# TFT-Display.net
KiCad netlist of a schematic drawn in Altium Designer
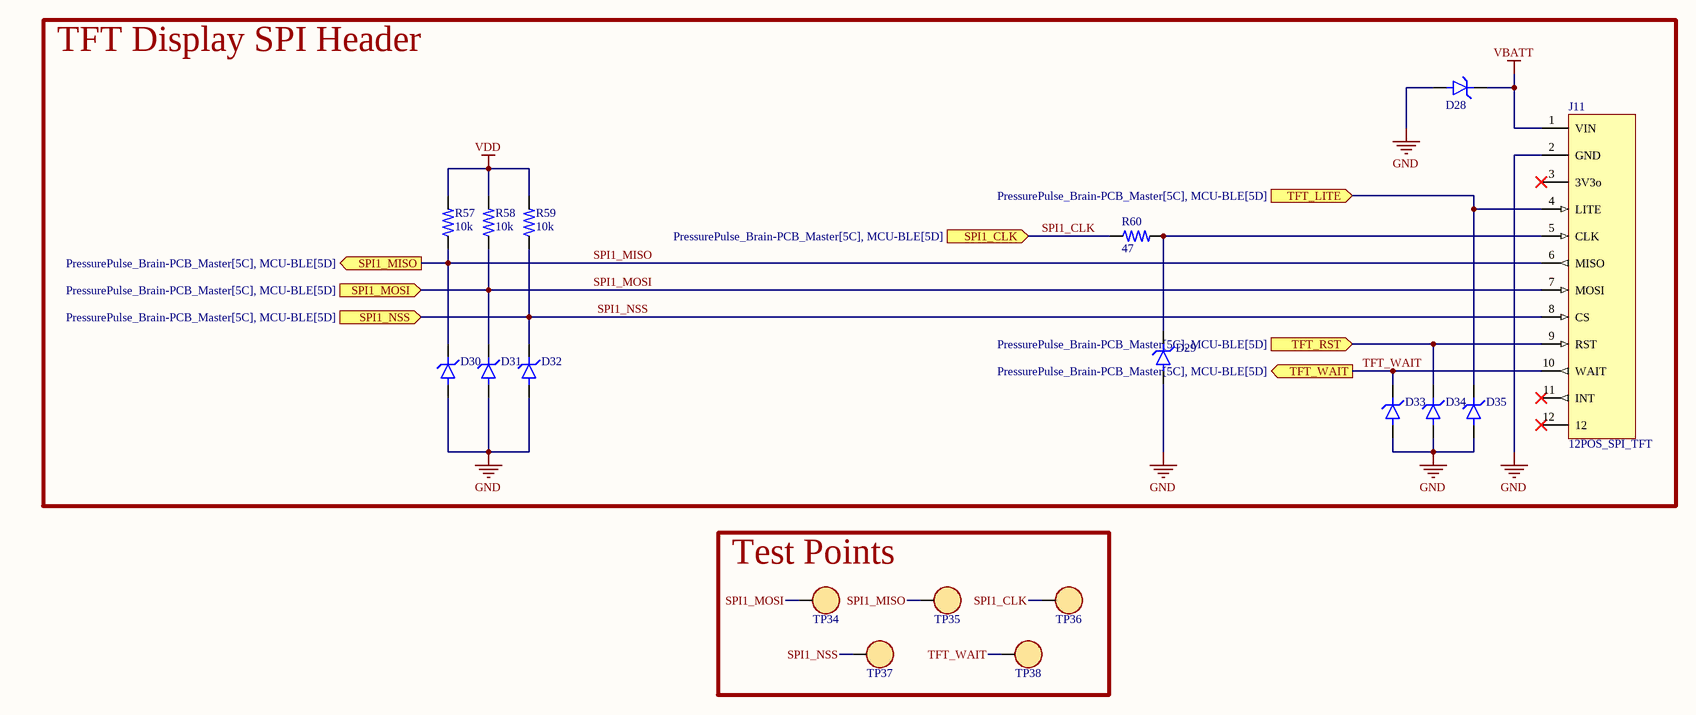
[diagram p0: TFT-Display.SchDoc]

(export (version "E")
  (design (tool "Eeschema 10.0.6"))
  (components
    (comp (ref "D28")
      (value "RCLAMP0521P.TCT")
      (footprint "PressurePulse:BDFN2C051V40")
      (description "25V Clamp 4A (8/20µs) Ipp Tvs Diode Surface Mount SLP1006P2")
      (fields (field (name "MFR") "BORN"))
      (libsource (lib "PressurePulse") (part "TVS DIODE"))
    )
    (comp (ref "D29")
      (value "RCLAMP0521P.TCT")
      (footprint "PressurePulse:BDFN2C051V40")
      (description "25V Clamp 4A (8/20µs) Ipp Tvs Diode Surface Mount SLP1006P2")
      (fields (field (name "MFR") "BORN"))
      (libsource (lib "PressurePulse") (part "TVS DIODE"))
    )
    (comp (ref "D30")
      (value "RCLAMP0521P.TCT")
      (footprint "PressurePulse:BDFN2C051V40")
      (description "25V Clamp 4A (8/20µs) Ipp Tvs Diode Surface Mount SLP1006P2")
      (fields (field (name "MFR") "BORN"))
      (libsource (lib "PressurePulse") (part "TVS DIODE"))
    )
    (comp (ref "D31")
      (value "RCLAMP0521P.TCT")
      (footprint "PressurePulse:BDFN2C051V40")
      (description "25V Clamp 4A (8/20µs) Ipp Tvs Diode Surface Mount SLP1006P2")
      (fields (field (name "MFR") "BORN"))
      (libsource (lib "PressurePulse") (part "TVS DIODE"))
    )
    (comp (ref "D32")
      (value "RCLAMP0521P.TCT")
      (footprint "PressurePulse:BDFN2C051V40")
      (description "25V Clamp 4A (8/20µs) Ipp Tvs Diode Surface Mount SLP1006P2")
      (fields (field (name "MFR") "BORN"))
      (libsource (lib "PressurePulse") (part "TVS DIODE"))
    )
    (comp (ref "D33")
      (value "RCLAMP0521P.TCT")
      (footprint "PressurePulse:BDFN2C051V40")
      (description "25V Clamp 4A (8/20µs) Ipp Tvs Diode Surface Mount SLP1006P2")
      (fields (field (name "MFR") "BORN"))
      (libsource (lib "PressurePulse") (part "TVS DIODE"))
    )
    (comp (ref "D34")
      (value "RCLAMP0521P.TCT")
      (footprint "PressurePulse:BDFN2C051V40")
      (description "25V Clamp 4A (8/20µs) Ipp Tvs Diode Surface Mount SLP1006P2")
      (fields (field (name "MFR") "BORN"))
      (libsource (lib "PressurePulse") (part "TVS DIODE"))
    )
    (comp (ref "D35")
      (value "RCLAMP0521P.TCT")
      (footprint "PressurePulse:BDFN2C051V40")
      (description "25V Clamp 4A (8/20µs) Ipp Tvs Diode Surface Mount SLP1006P2")
      (fields (field (name "MFR") "BORN"))
      (libsource (lib "PressurePulse") (part "TVS DIODE"))
    )
    (comp (ref "J11")
      (value "12POS_SPI_TFT")
      (footprint "PressurePulse:2.54MM-12POS_TFT")
      (libsource (lib "PressurePulse") (part "12POS_SPI_TFT"))
    )
    (comp (ref "R57")
      (value "10k")
      (footprint "PressurePulse:0402R")
      (description "Resistor")
      (fields (field (name "Comment") "RES"))
      (libsource (lib "PressurePulse") (part "RES"))
    )
    (comp (ref "R58")
      (value "10k")
      (footprint "PressurePulse:0402R")
      (description "Resistor")
      (fields (field (name "Comment") "RES"))
      (libsource (lib "PressurePulse") (part "RES"))
    )
    (comp (ref "R59")
      (value "10k")
      (footprint "PressurePulse:0402R")
      (description "Resistor")
      (fields (field (name "Comment") "RES"))
      (libsource (lib "PressurePulse") (part "RES"))
    )
    (comp (ref "R60")
      (value "47")
      (footprint "PressurePulse:0402R")
      (description "Resistor")
      (fields (field (name "Comment") "RES"))
      (libsource (lib "PressurePulse") (part "RES"))
    )
    (comp (ref "TP34")
      (value "RH-5019")
      (footprint "PressurePulse:TP - RH-5019")
      (fields (field (name "MFR") "ronghe"))
      (libsource (lib "PressurePulse") (part "TEST POINT"))
    )
    (comp (ref "TP35")
      (value "RH-5019")
      (footprint "PressurePulse:TP - RH-5019")
      (fields (field (name "MFR") "ronghe"))
      (libsource (lib "PressurePulse") (part "TEST POINT"))
    )
    (comp (ref "TP36")
      (value "RH-5019")
      (footprint "PressurePulse:TP - RH-5019")
      (fields (field (name "MFR") "ronghe"))
      (libsource (lib "PressurePulse") (part "TEST POINT"))
    )
    (comp (ref "TP37")
      (value "RH-5019")
      (footprint "PressurePulse:TP - RH-5019")
      (fields (field (name "MFR") "ronghe"))
      (libsource (lib "PressurePulse") (part "TEST POINT"))
    )
    (comp (ref "TP38")
      (value "RH-5019")
      (footprint "PressurePulse:TP - RH-5019")
      (fields (field (name "MFR") "ronghe"))
      (libsource (lib "PressurePulse") (part "TEST POINT"))
    )
  )
  (nets
    (net (code "1") (name "/SPI1_CLK") (class "Default")
      (node (ref "R60") (pin "1") (pinfunction "1_1") (pintype "passive"))
      (node (ref "TP36") (pin "1") (pinfunction "1_1") (pintype "passive"))
    )
    (net (code "2") (name "/SPI1_MISO") (class "Default")
      (node (ref "D30") (pin "K") (pinfunction "K_K") (pintype "passive"))
      (node (ref "J11") (pin "6") (pinfunction "MISO_6") (pintype "output"))
      (node (ref "R57") (pin "1") (pinfunction "1_1") (pintype "passive"))
      (node (ref "TP35") (pin "1") (pinfunction "1_1") (pintype "passive"))
    )
    (net (code "3") (name "/SPI1_MOSI") (class "Default")
      (node (ref "D31") (pin "K") (pinfunction "K_K") (pintype "passive"))
      (node (ref "J11") (pin "7") (pinfunction "MOSI_7") (pintype "input"))
      (node (ref "R58") (pin "1") (pinfunction "1_1") (pintype "passive"))
      (node (ref "TP34") (pin "1") (pinfunction "1_1") (pintype "passive"))
    )
    (net (code "4") (name "/SPI1_NSS") (class "Default")
      (node (ref "D32") (pin "K") (pinfunction "K_K") (pintype "passive"))
      (node (ref "J11") (pin "8") (pinfunction "CS_8") (pintype "input"))
      (node (ref "R59") (pin "1") (pinfunction "1_1") (pintype "passive"))
      (node (ref "TP37") (pin "1") (pinfunction "1_1") (pintype "passive"))
    )
    (net (code "5") (name "/TFT_LITE") (class "Default")
      (node (ref "D35") (pin "K") (pinfunction "K_K") (pintype "passive"))
      (node (ref "J11") (pin "4") (pinfunction "LITE_4") (pintype "input"))
    )
    (net (code "6") (name "/TFT_RST") (class "Default")
      (node (ref "D34") (pin "K") (pinfunction "K_K") (pintype "passive"))
      (node (ref "J11") (pin "9") (pinfunction "RST_9") (pintype "input"))
    )
    (net (code "7") (name "/TFT_WAIT") (class "Default")
      (node (ref "D33") (pin "K") (pinfunction "K_K") (pintype "passive"))
      (node (ref "J11") (pin "10") (pinfunction "WAIT_10") (pintype "output"))
      (node (ref "TP38") (pin "1") (pinfunction "1_1") (pintype "passive"))
    )
    (net (code "8") (name "GND") (class "Default")
      (node (ref "D28") (pin "A") (pinfunction "A_A") (pintype "passive"))
      (node (ref "D29") (pin "A") (pinfunction "A_A") (pintype "passive"))
      (node (ref "D30") (pin "A") (pinfunction "A_A") (pintype "passive"))
      (node (ref "D31") (pin "A") (pinfunction "A_A") (pintype "passive"))
      (node (ref "D32") (pin "A") (pinfunction "A_A") (pintype "passive"))
      (node (ref "D33") (pin "A") (pinfunction "A_A") (pintype "passive"))
      (node (ref "D34") (pin "A") (pinfunction "A_A") (pintype "passive"))
      (node (ref "D35") (pin "A") (pinfunction "A_A") (pintype "passive"))
      (node (ref "J11") (pin "2") (pinfunction "GND_2") (pintype "passive"))
    )
    (net (code "9") (name "Net-(J11-CLK)") (class "Default")
      (node (ref "D29") (pin "K") (pinfunction "K_K") (pintype "passive"))
      (node (ref "J11") (pin "5") (pinfunction "CLK_5") (pintype "input"))
      (node (ref "R60") (pin "2") (pinfunction "2_2") (pintype "passive"))
    )
    (net (code "10") (name "VBATT") (class "Default")
      (node (ref "D28") (pin "K") (pinfunction "K_K") (pintype "passive"))
      (node (ref "J11") (pin "1") (pinfunction "VIN_1") (pintype "power_in"))
    )
    (net (code "11") (name "VDD") (class "Default")
      (node (ref "R57") (pin "2") (pinfunction "2_2") (pintype "passive"))
      (node (ref "R58") (pin "2") (pinfunction "2_2") (pintype "passive"))
      (node (ref "R59") (pin "2") (pinfunction "2_2") (pintype "passive"))
    )
    (net (code "12") (name "unconnected-(J11-3V3o-Pad3)") (class "Default")
      (node (ref "J11") (pin "3") (pinfunction "3V3o_3") (pintype "passive+no_connect"))
    )
    (net (code "13") (name "unconnected-(J11-INT-Pad11)") (class "Default")
      (node (ref "J11") (pin "11") (pinfunction "INT_11") (pintype "output+no_connect"))
    )
    (net (code "14") (name "unconnected-(J11-Pad12)") (class "Default")
      (node (ref "J11") (pin "12") (pinfunction "12_12") (pintype "passive+no_connect"))
    )
  )
)
